# pi_ups.net
KiCad netlist of a schematic drawn in Altium Designer
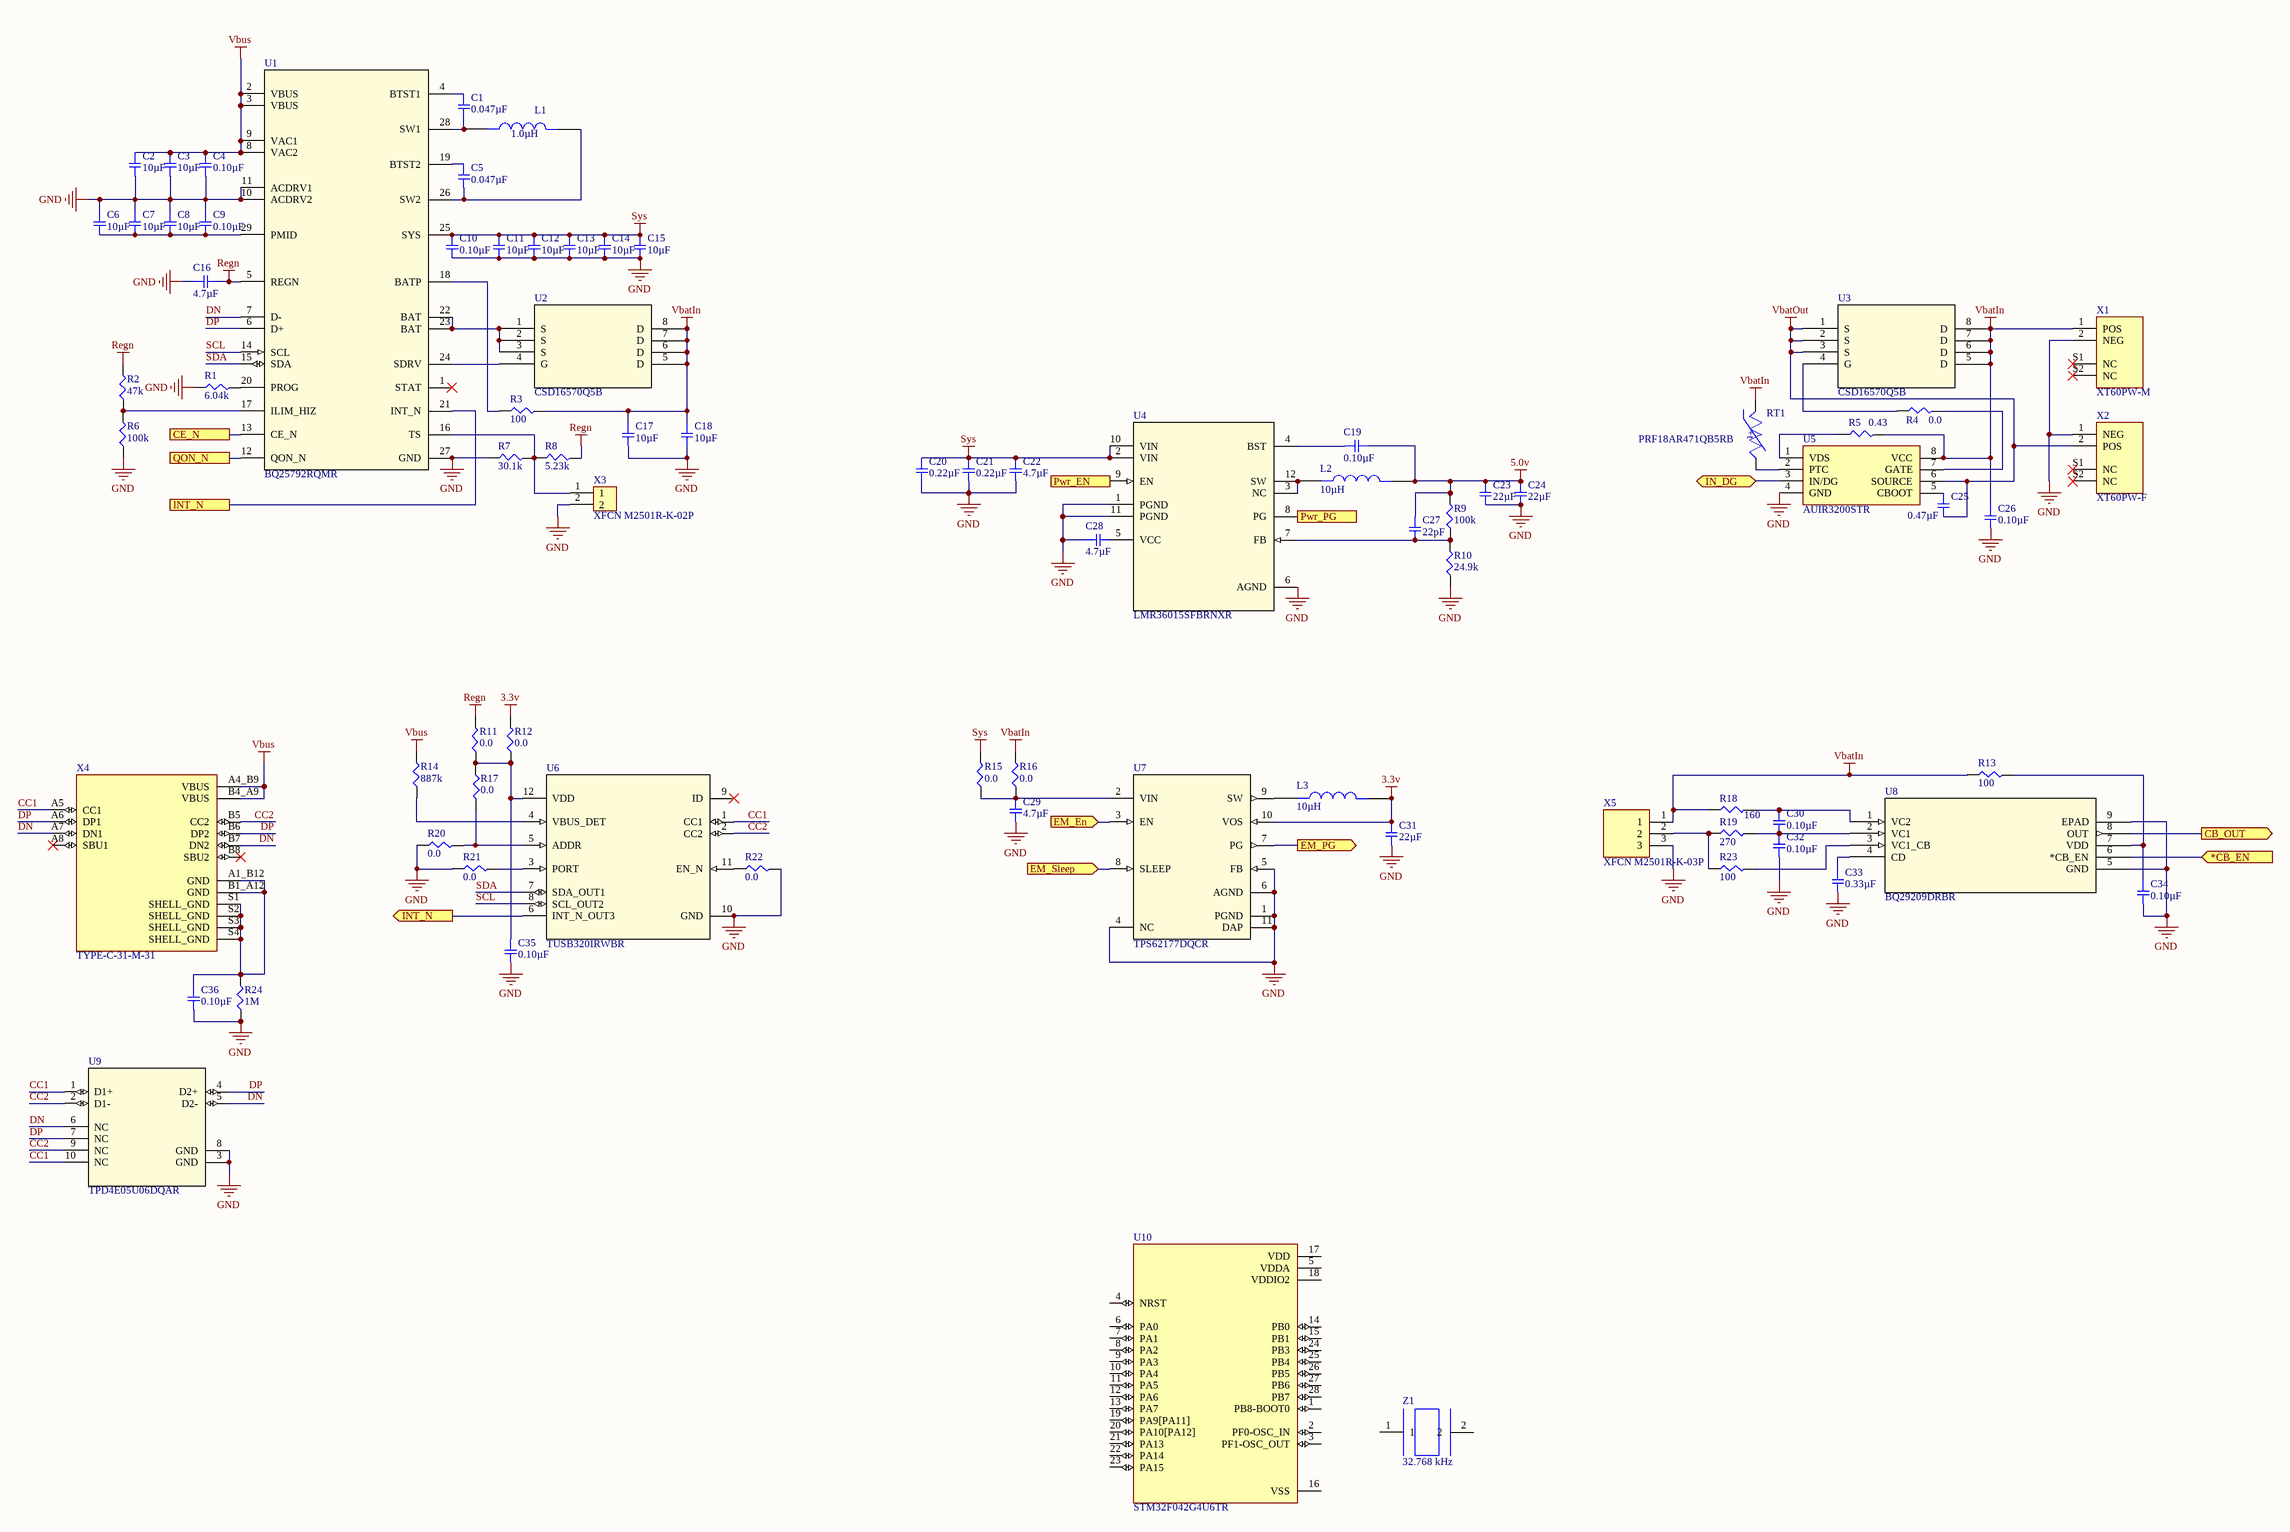
[diagram p0: pi_ups.SchDoc]

(export (version "E")
  (design (tool "Eeschema 10.0.6"))
  (components
    (comp (ref "C1")
      (value "0.047µF")
      (footprint "SMD-0402C")
      (description "CAP CER 0.047UF 50V X5R 0402")
      (fields
        (field (name "DIGI-KEY PART NUMBER") "490-12705-1-ND")
        (field (name "PART NUMBER") "GRM155R61H473KE19D")
      )
      (libsource (lib "capacitor_murata_0402") (part "GRM155R61H473KE19D"))
    )
    (comp (ref "C2")
      (value "10µF")
      (footprint "SMD-0805C")
      (description "CAP CER 10UF 35V X5R 0805")
      (fields
        (field (name "DIGI-KEY PART NUMBER") "490-10514-1-ND")
        (field (name "PART NUMBER") "GRM21BR6YA106KE43L")
      )
      (libsource (lib "capacitor_murata_0805") (part "GRM21BR6YA106KE43L"))
    )
    (comp (ref "C3")
      (value "10µF")
      (footprint "SMD-0805C")
      (description "CAP CER 10UF 35V X5R 0805")
      (fields
        (field (name "DIGI-KEY PART NUMBER") "490-10514-1-ND")
        (field (name "PART NUMBER") "GRM21BR6YA106KE43L")
      )
      (libsource (lib "capacitor_murata_0805") (part "GRM21BR6YA106KE43L"))
    )
    (comp (ref "C4")
      (value "0.10µF")
      (footprint "SMD-0402C")
      (description "CAP CER 0.1UF 50V X7R 0402")
      (fields
        (field (name "DIGI-KEY PART NUMBER") "490-10701-1-ND")
        (field (name "PART NUMBER") "GRM155R71H104ME14D")
      )
      (libsource (lib "capacitor_murata_0402") (part "GRM155R71H104ME14D"))
    )
    (comp (ref "C5")
      (value "0.047µF")
      (footprint "SMD-0402C")
      (description "CAP CER 0.047UF 50V X5R 0402")
      (fields
        (field (name "DIGI-KEY PART NUMBER") "490-12705-1-ND")
        (field (name "PART NUMBER") "GRM155R61H473KE19D")
      )
      (libsource (lib "capacitor_murata_0402") (part "GRM155R61H473KE19D"))
    )
    (comp (ref "C6")
      (value "10µF")
      (footprint "SMD-0805C")
      (description "CAP CER 10UF 35V X5R 0805")
      (fields
        (field (name "DIGI-KEY PART NUMBER") "490-10514-1-ND")
        (field (name "PART NUMBER") "GRM21BR6YA106KE43L")
      )
      (libsource (lib "capacitor_murata_0805") (part "GRM21BR6YA106KE43L"))
    )
    (comp (ref "C7")
      (value "10µF")
      (footprint "SMD-0805C")
      (description "CAP CER 10UF 35V X5R 0805")
      (fields
        (field (name "DIGI-KEY PART NUMBER") "490-10514-1-ND")
        (field (name "PART NUMBER") "GRM21BR6YA106KE43L")
      )
      (libsource (lib "capacitor_murata_0805") (part "GRM21BR6YA106KE43L"))
    )
    (comp (ref "C8")
      (value "10µF")
      (footprint "SMD-0805C")
      (description "CAP CER 10UF 35V X5R 0805")
      (fields
        (field (name "DIGI-KEY PART NUMBER") "490-10514-1-ND")
        (field (name "PART NUMBER") "GRM21BR6YA106KE43L")
      )
      (libsource (lib "capacitor_murata_0805") (part "GRM21BR6YA106KE43L"))
    )
    (comp (ref "C9")
      (value "0.10µF")
      (footprint "SMD-0402C")
      (description "CAP CER 0.1UF 50V X7R 0402")
      (fields
        (field (name "DIGI-KEY PART NUMBER") "490-10701-1-ND")
        (field (name "PART NUMBER") "GRM155R71H104ME14D")
      )
      (libsource (lib "capacitor_murata_0402") (part "GRM155R71H104ME14D"))
    )
    (comp (ref "C10")
      (value "0.10µF")
      (footprint "SMD-0402C")
      (description "CAP CER 0.1UF 50V X7R 0402")
      (fields
        (field (name "DIGI-KEY PART NUMBER") "490-10701-1-ND")
        (field (name "PART NUMBER") "GRM155R71H104ME14D")
      )
      (libsource (lib "capacitor_murata_0402") (part "GRM155R71H104ME14D"))
    )
    (comp (ref "C11")
      (value "10µF")
      (footprint "SMD-0805C")
      (description "CAP CER 10UF 35V X5R 0805")
      (fields
        (field (name "DIGI-KEY PART NUMBER") "490-10514-1-ND")
        (field (name "PART NUMBER") "GRM21BR6YA106KE43L")
      )
      (libsource (lib "capacitor_murata_0805") (part "GRM21BR6YA106KE43L"))
    )
    (comp (ref "C12")
      (value "10µF")
      (footprint "SMD-0805C")
      (description "CAP CER 10UF 35V X5R 0805")
      (fields
        (field (name "DIGI-KEY PART NUMBER") "490-10514-1-ND")
        (field (name "PART NUMBER") "GRM21BR6YA106KE43L")
      )
      (libsource (lib "capacitor_murata_0805") (part "GRM21BR6YA106KE43L"))
    )
    (comp (ref "C13")
      (value "10µF")
      (footprint "SMD-0805C")
      (description "CAP CER 10UF 35V X5R 0805")
      (fields
        (field (name "DIGI-KEY PART NUMBER") "490-10514-1-ND")
        (field (name "PART NUMBER") "GRM21BR6YA106KE43L")
      )
      (libsource (lib "capacitor_murata_0805") (part "GRM21BR6YA106KE43L"))
    )
    (comp (ref "C14")
      (value "10µF")
      (footprint "SMD-0805C")
      (description "CAP CER 10UF 35V X5R 0805")
      (fields
        (field (name "DIGI-KEY PART NUMBER") "490-10514-1-ND")
        (field (name "PART NUMBER") "GRM21BR6YA106KE43L")
      )
      (libsource (lib "capacitor_murata_0805") (part "GRM21BR6YA106KE43L"))
    )
    (comp (ref "C15")
      (value "10µF")
      (footprint "SMD-0805C")
      (description "CAP CER 10UF 35V X5R 0805")
      (fields
        (field (name "DIGI-KEY PART NUMBER") "490-10514-1-ND")
        (field (name "PART NUMBER") "GRM21BR6YA106KE43L")
      )
      (libsource (lib "capacitor_murata_0805") (part "GRM21BR6YA106KE43L"))
    )
    (comp (ref "C16")
      (value "4.7µF")
      (footprint "SMD-0805C")
      (description "CAP CER 4.7UF 50V X5R 0805")
      (fields
        (field (name "DIGI-KEY PART NUMBER") "490-10751-1-ND")
        (field (name "PART NUMBER") "GRM21BR61H475KE51L")
      )
      (libsource (lib "capacitor_murata_0805") (part "GRM21BR61H475KE51L"))
    )
    (comp (ref "C17")
      (value "10µF")
      (footprint "SMD-0805C")
      (description "CAP CER 10UF 35V X5R 0805")
      (fields
        (field (name "DIGI-KEY PART NUMBER") "490-10514-1-ND")
        (field (name "PART NUMBER") "GRM21BR6YA106KE43L")
      )
      (libsource (lib "capacitor_murata_0805") (part "GRM21BR6YA106KE43L"))
    )
    (comp (ref "C18")
      (value "10µF")
      (footprint "SMD-0805C")
      (description "CAP CER 10UF 35V X5R 0805")
      (fields
        (field (name "DIGI-KEY PART NUMBER") "490-10514-1-ND")
        (field (name "PART NUMBER") "GRM21BR6YA106KE43L")
      )
      (libsource (lib "capacitor_murata_0805") (part "GRM21BR6YA106KE43L"))
    )
    (comp (ref "C19")
      (value "0.10µF")
      (footprint "SMD-0402C")
      (description "CAP CER 0.1UF 50V X7R 0402")
      (fields
        (field (name "DIGI-KEY PART NUMBER") "490-10701-1-ND")
        (field (name "PART NUMBER") "GRM155R71H104ME14D")
      )
      (libsource (lib "capacitor_murata_0402") (part "GRM155R71H104ME14D"))
    )
    (comp (ref "C20")
      (value "0.22µF")
      (footprint "SMD-0603C")
      (description "CAP CER 0.22UF 50V X5R 0603")
      (fields
        (field (name "DIGI-KEY PART NUMBER") "490-12739-1-ND")
        (field (name "PART NUMBER") "GRM188R61H224KAC4D")
      )
      (libsource (lib "capacitor_murata_0603") (part "GRM188R61H224KAC4D"))
    )
    (comp (ref "C21")
      (value "0.22µF")
      (footprint "SMD-0603C")
      (description "CAP CER 0.22UF 50V X5R 0603")
      (fields
        (field (name "DIGI-KEY PART NUMBER") "490-12739-1-ND")
        (field (name "PART NUMBER") "GRM188R61H224KAC4D")
      )
      (libsource (lib "capacitor_murata_0603") (part "GRM188R61H224KAC4D"))
    )
    (comp (ref "C22")
      (value "4.7µF")
      (footprint "SMD-0805C")
      (description "CAP CER 4.7UF 50V X5R 0805")
      (fields
        (field (name "DIGI-KEY PART NUMBER") "490-10751-1-ND")
        (field (name "PART NUMBER") "GRM21BR61H475KE51L")
      )
      (libsource (lib "capacitor_murata_0805") (part "GRM21BR61H475KE51L"))
    )
    (comp (ref "C23")
      (value "22µF")
      (footprint "SMD-0805C")
      (description "CAP CER 22UF 10V X5R 0805")
      (fields
        (field (name "DIGI-KEY PART NUMBER") "490-9951-1-ND")
        (field (name "PART NUMBER") "GRM219R61A226MEA0D")
      )
      (libsource (lib "capacitor_murata_0805") (part "GRM219R61A226MEA0D"))
    )
    (comp (ref "C24")
      (value "22µF")
      (footprint "SMD-0805C")
      (description "CAP CER 22UF 10V X5R 0805")
      (fields
        (field (name "DIGI-KEY PART NUMBER") "490-9951-1-ND")
        (field (name "PART NUMBER") "GRM219R61A226MEA0D")
      )
      (libsource (lib "capacitor_murata_0805") (part "GRM219R61A226MEA0D"))
    )
    (comp (ref "C25")
      (value "0.47µF")
      (footprint "SMD-0603C")
      (description "CAP CER 0.47UF 16V X7R 0603")
      (fields
        (field (name "DIGI-KEY PART NUMBER") "490-4775-1-ND")
        (field (name "PART NUMBER") "GCM188R71C474KA55D")
      )
      (libsource (lib "capacitor_murata_0603") (part "GCM188R71C474KA55D"))
    )
    (comp (ref "C26")
      (value "0.10µF")
      (footprint "SMD-0402C")
      (description "CAP CER 0.1UF 50V X7R 0402")
      (fields
        (field (name "DIGI-KEY PART NUMBER") "490-10701-1-ND")
        (field (name "PART NUMBER") "GRM155R71H104ME14D")
      )
      (libsource (lib "capacitor_murata_0402") (part "GRM155R71H104ME14D"))
    )
    (comp (ref "C27")
      (value "22pF")
      (footprint "SMD-0402C")
      (description "CAP CER 22PF 50V NP0 0402")
      (fields
        (field (name "DIGI-KEY PART NUMBER") "490-9648-1-ND")
        (field (name "PART NUMBER") "GCM1555C1H220JA16D")
      )
      (libsource (lib "capacitor_murata_0402") (part "GCM1555C1H220JA16D"))
    )
    (comp (ref "C28")
      (value "4.7µF")
      (footprint "SMD-0805C")
      (description "CAP CER 4.7UF 50V X5R 0805")
      (fields
        (field (name "DIGI-KEY PART NUMBER") "490-10751-1-ND")
        (field (name "PART NUMBER") "GRM21BR61H475KE51L")
      )
      (libsource (lib "capacitor_murata_0805") (part "GRM21BR61H475KE51L"))
    )
    (comp (ref "C29")
      (value "4.7µF")
      (footprint "SMD-0805C")
      (description "CAP CER 4.7UF 50V X5R 0805")
      (fields
        (field (name "DIGI-KEY PART NUMBER") "490-10751-1-ND")
        (field (name "PART NUMBER") "GRM21BR61H475KE51L")
      )
      (libsource (lib "capacitor_murata_0805") (part "GRM21BR61H475KE51L"))
    )
    (comp (ref "C30")
      (value "0.10µF")
      (footprint "SMD-0402C")
      (description "CAP CER 0.1UF 50V X7R 0402")
      (fields
        (field (name "DIGI-KEY PART NUMBER") "490-10701-1-ND")
        (field (name "PART NUMBER") "GRM155R71H104ME14D")
      )
      (libsource (lib "capacitor_murata_0402") (part "GRM155R71H104ME14D"))
    )
    (comp (ref "C31")
      (value "22µF")
      (footprint "SMD-0805C")
      (description "CAP CER 22UF 10V X5R 0805")
      (fields
        (field (name "DIGI-KEY PART NUMBER") "490-9951-1-ND")
        (field (name "PART NUMBER") "GRM219R61A226MEA0D")
      )
      (libsource (lib "capacitor_murata_0805") (part "GRM219R61A226MEA0D"))
    )
    (comp (ref "C32")
      (value "0.10µF")
      (footprint "SMD-0402C")
      (description "CAP CER 0.1UF 50V X7R 0402")
      (fields
        (field (name "DIGI-KEY PART NUMBER") "490-10701-1-ND")
        (field (name "PART NUMBER") "GRM155R71H104ME14D")
      )
      (libsource (lib "capacitor_murata_0402") (part "GRM155R71H104ME14D"))
    )
    (comp (ref "C33")
      (value "0.33µF")
      (footprint "SMD-0603C")
      (description "CAP CER 0.33UF 16V X7R 0603")
      (fields
        (field (name "DIGI-KEY PART NUMBER") "490-6050-1-ND")
        (field (name "PART NUMBER") "GCM188R71C334KA37D")
      )
      (libsource (lib "capacitor_murata_0603") (part "GCM188R71C334KA37D"))
    )
    (comp (ref "C34")
      (value "0.10µF")
      (footprint "SMD-0402C")
      (description "CAP CER 0.1UF 50V X7R 0402")
      (fields
        (field (name "DIGI-KEY PART NUMBER") "490-10701-1-ND")
        (field (name "PART NUMBER") "GRM155R71H104ME14D")
      )
      (libsource (lib "capacitor_murata_0402") (part "GRM155R71H104ME14D"))
    )
    (comp (ref "C35")
      (value "0.10µF")
      (footprint "SMD-0402C")
      (description "CAP CER 0.1UF 50V X7R 0402")
      (fields
        (field (name "DIGI-KEY PART NUMBER") "490-10701-1-ND")
        (field (name "PART NUMBER") "GRM155R71H104ME14D")
      )
      (libsource (lib "capacitor_murata_0402") (part "GRM155R71H104ME14D"))
    )
    (comp (ref "C36")
      (value "0.10µF")
      (footprint "SMD-0402C")
      (description "CAP CER 0.1UF 50V X7R 0402")
      (fields
        (field (name "DIGI-KEY PART NUMBER") "490-10701-1-ND")
        (field (name "PART NUMBER") "GRM155R71H104ME14D")
      )
      (libsource (lib "capacitor_murata_0402") (part "GRM155R71H104ME14D"))
    )
    (comp (ref "L1")
      (value "1.0µH")
      (footprint "SPM6530T-1R0M120")
      (description "Shielded Wirewound Inductor 1.0uH 13.2A 0.0071ohms 7.1x6.5x3mm")
      (fields (field (name "PART NUMBER") "SPM6530T-1R0M120") (field (name "MANUFACTURER") "TDK"))
      (libsource (lib "common") (part "SPM6530T-1R0M120"))
    )
    (comp (ref "L2")
      (value "10µH")
      (footprint "4020")
      (description "1.9A 10uH ±20% 1.9A 165mΩ SMD,4.5x4.1x1.8mm Inductors (SMD) ROHS")
      (fields (field (name "MANUFACTURER") "KOHERelec") (field (name "PART NUMBER") "MDA4020-100M"))
      (libsource (lib "common") (part "MDA4020-100M"))
    )
    (comp (ref "L3")
      (value "10µH")
      (footprint "4020")
      (description "1.9A 10uH ±20% 1.9A 165mΩ SMD,4.5x4.1x1.8mm Inductors (SMD) ROHS")
      (fields (field (name "MANUFACTURER") "KOHERelec") (field (name "PART NUMBER") "MDA4020-100M"))
      (libsource (lib "common") (part "MDA4020-100M"))
    )
    (comp (ref "R1")
      (value "6.04k")
      (footprint "SMD-0402-RES")
      (description "RES SMD 6.04K OHM 1% 1/10W 0402")
      (fields
        (field (name "PART NUMBER") "ERJ-2RKF6041X")
        (field (name "DIGI-KEY PART NUMBER") "P6.04KLCT-ND")
      )
      (libsource (lib "Panasonic_ERJ_0402") (part "ERJ-2RKF6041X"))
    )
    (comp (ref "R2")
      (value "47k")
      (footprint "SMD-0402-RES")
      (description "RES SMD 47K OHM 1% 1/10W 0402")
      (fields
        (field (name "PART NUMBER") "ERJ-2RKF4702X")
        (field (name "DIGI-KEY PART NUMBER") "P47.0KLCT-ND")
      )
      (libsource (lib "Panasonic_ERJ_0402") (part "ERJ-2RKF4702X"))
    )
    (comp (ref "R3")
      (value "100")
      (footprint "SMD-0402-RES")
      (description "RES SMD 100 OHM 5% 1/5W 0402")
      (fields (field (name "PART NUMBER") "ERJ-PA2J101X") (field (name "DIGI-KEY PART NUMBER") "P17187CT-ND"))
      (libsource (lib "Panasonic_ERJ_0402") (part "ERJ-PA2J101X"))
    )
    (comp (ref "R4")
      (value "0.0")
      (footprint "SMD-0402-RES")
      (description "RES SMD 0.0OHM JUMPER 1/10W 0402")
      (fields (field (name "PART NUMBER") "ERJ-2GE0R00X") (field (name "DIGI-KEY PART NUMBER") "P0.0JCT-ND"))
      (libsource (lib "Panasonic_ERJ_0402") (part "ERJ-2GE0R00X"))
    )
    (comp (ref "R5")
      (value "0.43")
      (footprint "SMD-0402-RES")
      (description "RES SMD 0.43 OHM 1% 1/6W 0402")
      (fields (field (name "PART NUMBER") "ERJ-2BQFR43X") (field (name "DIGI-KEY PART NUMBER") "P.43AKCT-ND"))
      (libsource (lib "Panasonic_ERJ_0402") (part "ERJ-2BQFR43X"))
    )
    (comp (ref "R6")
      (value "100k")
      (footprint "SMD-0402-RES")
      (description "RES SMD 100K OHM 1% 1/10W 0402")
      (fields
        (field (name "PART NUMBER") "ERJ-2RKF1003X")
        (field (name "DIGI-KEY PART NUMBER") "P100KLCT-ND")
      )
      (libsource (lib "Panasonic_ERJ_0402") (part "ERJ-2RKF1003X"))
    )
    (comp (ref "R7")
      (value "30.1k")
      (footprint "SMD-0402-RES")
      (description "RES SMD 30.1K OHM 1% 1/10W 0402")
      (fields
        (field (name "PART NUMBER") "ERJ-2RKF3012X")
        (field (name "DIGI-KEY PART NUMBER") "P30.1KLCT-ND")
      )
      (libsource (lib "Panasonic_ERJ_0402") (part "ERJ-2RKF3012X"))
    )
    (comp (ref "R8")
      (value "5.23k")
      (footprint "SMD-0402-RES")
      (description "RES SMD 5.23K OHM 1% 1/10W 0402")
      (fields
        (field (name "PART NUMBER") "ERJ-2RKF5231X")
        (field (name "DIGI-KEY PART NUMBER") "P5.23KLCT-ND")
      )
      (libsource (lib "Panasonic_ERJ_0402") (part "ERJ-2RKF5231X"))
    )
    (comp (ref "R9")
      (value "100k")
      (footprint "SMD-0402-RES")
      (description "RES SMD 100K OHM 1% 1/10W 0402")
      (fields
        (field (name "PART NUMBER") "ERJ-2RKF1003X")
        (field (name "DIGI-KEY PART NUMBER") "P100KLCT-ND")
      )
      (libsource (lib "Panasonic_ERJ_0402") (part "ERJ-2RKF1003X"))
    )
    (comp (ref "R10")
      (value "24.9k")
      (footprint "SMD-0402-RES")
      (description "RES SMD 24.9K OHM 1% 1/10W 0402")
      (fields
        (field (name "PART NUMBER") "ERJ-2RKF2492X")
        (field (name "DIGI-KEY PART NUMBER") "P24.9KLCT-ND")
      )
      (libsource (lib "Panasonic_ERJ_0402") (part "ERJ-2RKF2492X"))
    )
    (comp (ref "R11")
      (value "0.0")
      (footprint "SMD-0402-RES")
      (description "RES SMD 0.0OHM JUMPER 1/10W 0402")
      (fields (field (name "PART NUMBER") "ERJ-2GE0R00X") (field (name "DIGI-KEY PART NUMBER") "P0.0JCT-ND"))
      (libsource (lib "Panasonic_ERJ_0402") (part "ERJ-2GE0R00X"))
    )
    (comp (ref "R12")
      (value "0.0")
      (footprint "SMD-0402-RES")
      (description "RES SMD 0.0OHM JUMPER 1/10W 0402")
      (fields (field (name "PART NUMBER") "ERJ-2GE0R00X") (field (name "DIGI-KEY PART NUMBER") "P0.0JCT-ND"))
      (libsource (lib "Panasonic_ERJ_0402") (part "ERJ-2GE0R00X"))
    )
    (comp (ref "R13")
      (value "100")
      (footprint "SMD-0402-RES")
      (description "RES SMD 100 OHM 5% 1/5W 0402")
      (fields (field (name "PART NUMBER") "ERJ-PA2J101X") (field (name "DIGI-KEY PART NUMBER") "P17187CT-ND"))
      (libsource (lib "Panasonic_ERJ_0402") (part "ERJ-PA2J101X"))
    )
    (comp (ref "R14")
      (value "887k")
      (footprint "SMD-0402-RES")
      (description "RES SMD 887K OHM 1% 1/10W 0402")
      (fields
        (field (name "PART NUMBER") "ERJ-2RKF8873X")
        (field (name "DIGI-KEY PART NUMBER") "P887KLCT-ND")
      )
      (libsource (lib "Panasonic_ERJ_0402") (part "ERJ-2RKF8873X"))
    )
    (comp (ref "R15")
      (value "0.0")
      (footprint "SMD-0402-RES")
      (description "RES SMD 0.0OHM JUMPER 1/10W 0402")
      (fields (field (name "PART NUMBER") "ERJ-2GE0R00X") (field (name "DIGI-KEY PART NUMBER") "P0.0JCT-ND"))
      (libsource (lib "Panasonic_ERJ_0402") (part "ERJ-2GE0R00X"))
    )
    (comp (ref "R16")
      (value "0.0")
      (footprint "SMD-0402-RES")
      (description "RES SMD 0.0OHM JUMPER 1/10W 0402")
      (fields (field (name "PART NUMBER") "ERJ-2GE0R00X") (field (name "DIGI-KEY PART NUMBER") "P0.0JCT-ND"))
      (libsource (lib "Panasonic_ERJ_0402") (part "ERJ-2GE0R00X"))
    )
    (comp (ref "R17")
      (value "0.0")
      (footprint "SMD-0402-RES")
      (description "RES SMD 0.0OHM JUMPER 1/10W 0402")
      (fields (field (name "PART NUMBER") "ERJ-2GE0R00X") (field (name "DIGI-KEY PART NUMBER") "P0.0JCT-ND"))
      (libsource (lib "Panasonic_ERJ_0402") (part "ERJ-2GE0R00X"))
    )
    (comp (ref "R18")
      (value "160")
      (footprint "SMD-0402-RES")
      (description "RES SMD 160 OHM 5% 1/10W 0402")
      (fields (field (name "PART NUMBER") "ERJ-2GEJ161X") (field (name "DIGI-KEY PART NUMBER") "P160JCT-ND"))
      (libsource (lib "Panasonic_ERJ_0402") (part "ERJ-2GEJ161X"))
    )
    (comp (ref "R19")
      (value "270")
      (footprint "SMD-0402-RES")
      (description "RES SMD 270 OHM 5% 1/10W 0402")
      (fields (field (name "PART NUMBER") "ERJ-2GEJ271X") (field (name "DIGI-KEY PART NUMBER") "P270JCT-ND"))
      (libsource (lib "Panasonic_ERJ_0402") (part "ERJ-2GEJ271X"))
    )
    (comp (ref "R20")
      (value "0.0")
      (footprint "SMD-0402-RES")
      (description "RES SMD 0.0OHM JUMPER 1/10W 0402")
      (fields (field (name "PART NUMBER") "ERJ-2GE0R00X") (field (name "DIGI-KEY PART NUMBER") "P0.0JCT-ND"))
      (libsource (lib "Panasonic_ERJ_0402") (part "ERJ-2GE0R00X"))
    )
    (comp (ref "R21")
      (value "0.0")
      (footprint "SMD-0402-RES")
      (description "RES SMD 0.0OHM JUMPER 1/10W 0402")
      (fields (field (name "PART NUMBER") "ERJ-2GE0R00X") (field (name "DIGI-KEY PART NUMBER") "P0.0JCT-ND"))
      (libsource (lib "Panasonic_ERJ_0402") (part "ERJ-2GE0R00X"))
    )
    (comp (ref "R22")
      (value "0.0")
      (footprint "SMD-0402-RES")
      (description "RES SMD 0.0OHM JUMPER 1/10W 0402")
      (fields (field (name "PART NUMBER") "ERJ-2GE0R00X") (field (name "DIGI-KEY PART NUMBER") "P0.0JCT-ND"))
      (libsource (lib "Panasonic_ERJ_0402") (part "ERJ-2GE0R00X"))
    )
    (comp (ref "R23")
      (value "100")
      (footprint "SMD-0402-RES")
      (description "RES SMD 100 OHM 5% 1/5W 0402")
      (fields (field (name "PART NUMBER") "ERJ-PA2J101X") (field (name "DIGI-KEY PART NUMBER") "P17187CT-ND"))
      (libsource (lib "Panasonic_ERJ_0402") (part "ERJ-PA2J101X"))
    )
    (comp (ref "R24")
      (value "1M")
      (footprint "SMD-0402-RES")
      (description "RES SMD 1M OHM 5% 1/5W 0402")
      (fields (field (name "PART NUMBER") "ERJ-PA2J105X") (field (name "DIGI-KEY PART NUMBER") "P17211CT-ND"))
      (libsource (lib "Panasonic_ERJ_0402") (part "ERJ-PA2J105X"))
    )
    (comp (ref "RT1")
      (value "PRF18AR471QB5RB")
      (footprint "THRMC1608X95N")
      (description "PTC Thermistor 470 Ohms 0603 (1608 Metric)")
      (fields
        (field (name "MANUFACTURER") "Murata Electronics North America")
        (field (name "LCSC PART NUMBER") "C152554")
      )
      (libsource (lib "common") (part "PRF18AR471QB5RB"))
    )
    (comp (ref "U1")
      (value "BQ25792RQMR")
      (footprint "RQM0029A-MFG")
      (fields
        (field (name "MANUFACTURER") "Texas Instruments")
        (field (name "LCSC PART NUMBER") "C2862876")
        (field (name "COPYRIGHT") "Copyright (C) 2022 Ultra Librarian. All rights reserved.")
      )
      (libsource (lib "chips") (part "BQ25792RQMR"))
    )
    (comp (ref "U2")
      (value "CSD16570Q5B")
      (footprint "DNK8")
      (description "25-V, N channel NexFET™ power MOSFET, single SON 5 mm x 6 mm, 0.82 mOhm")
      (fields
        (field (name "MANUFACTURER") "Texas Instruments")
        (field (name "LCSC PART NUMBER") "C473359")
        (field (name "COPYRIGHT") "Copyright (C) 2022 Ultra Librarian. All rights reserved.")
      )
      (libsource (lib "chips") (part "CSD16570Q5B"))
    )
    (comp (ref "U3")
      (value "CSD16570Q5B")
      (footprint "DNK8")
      (description "25-V, N channel NexFET™ power MOSFET, single SON 5 mm x 6 mm, 0.82 mOhm")
      (fields
        (field (name "MANUFACTURER") "Texas Instruments")
        (field (name "LCSC PART NUMBER") "C473359")
        (field (name "COPYRIGHT") "Copyright (C) 2022 Ultra Librarian. All rights reserved.")
      )
      (libsource (lib "chips") (part "CSD16570Q5B"))
    )
    (comp (ref "U4")
      (value "LMR36015SFBRNXR")
      (footprint "RNX0012B")
      (description "4.2-V to 60-V, 1.5-A ultra-small synchronous step-down converter with extended temperature")
      (fields
        (field (name "MANUFACTURER") "Texas Instruments")
        (field (name "COPYRIGHT") "Copyright (C) 2022 Ultra Librarian. All rights reserved.")
      )
      (libsource (lib "chips") (part "LMR36015SFBRNXR"))
    )
    (comp (ref "U5")
      (value "AUIR3200STR")
      (footprint "SOIC127P600X175-8N")
      (fields
        (field (name "MANUFACTURER") "Infineon Technologies")
        (field (name "LCSC PART NUMBER") "C97698")
      )
      (libsource (lib "chips") (part "AUIR3200STR"))
    )
    (comp (ref "U6")
      (value "TUSB320IRWBR")
      (footprint "RWB0012A")
      (description "USB Type-C configuration channel logic and port control")
      (fields
        (field (name "MANUFACTURER") "Texas Instruments")
        (field (name "LCSC PART NUMBER") "C80170")
        (field (name "COPYRIGHT") "Copyright (C) 2022 Ultra Librarian. All rights reserved.")
      )
      (libsource (lib "chips") (part "TUSB320IRWBR"))
    )
    (comp (ref "U7")
      (value "TPS62177DQCR")
      (footprint "DQC0010A")
      (description "28V, 0.5A Step-Down Converter with SNOOZE Mode")
      (fields
        (field (name "MANUFACTURER") "Texas Instruments")
        (field (name "LCSC PART NUMBER") "C91241")
        (field (name "COPYRIGHT") "Copyright (C) 2022 Ultra Librarian. All rights reserved.")
      )
      (libsource (lib "chips") (part "TPS62177DQCR"))
    )
    (comp (ref "U8")
      (value "BQ29209DRBR")
      (footprint "DRB8_1P6X2P4")
      (description "Voltage Protection with Automatic Cell Balance For 2-Cell Li-Ion Batteries, OVP=4.30V")
      (fields
        (field (name "MANUFACTURER") "Texas Instruments")
        (field (name "LCSC PART NUMBER") "C139352")
        (field (name "COPYRIGHT") "Copyright (C) 2022 Ultra Librarian. All rights reserved.")
      )
      (libsource (lib "chips") (part "BQ29209DRBR"))
    )
    (comp (ref "U9")
      (value "TPD4E05U06DQAR")
      (footprint "DQA0010A")
      (description "Quad 0.5-pF, 5.5-V, ±12-kV ESD protection diode for USB,  HDMI & High Speed Interfaces")
      (fields
        (field (name "MANUFACTURER") "Texas Instruments")
        (field (name "LCSC PART NUMBER") "C138714")
        (field (name "COPYRIGHT") "Copyright (C) 2022 Ultra Librarian. All rights reserved.")
      )
      (libsource (lib "chips") (part "TPD4E05U06DQAR"))
    )
    (comp (ref "U10")
      (value "STM32F042G4U6TR")
      (footprint "IC_STM32F042G4U6TR")
      (description "ARM® Cortex®-M0 STM32F0 Microcontroller IC 32-Bit 48MHz 32KB (32K x 8) FLASH 28-UFQFPN (4x4)")
      (fields (field (name "MANUFACTURER") "STMicroelectronics") (field (name "LCSC PART NUMBER") "C88048"))
      (libsource (lib "chips") (part "STM32F042G4U6TR"))
    )
    (comp (ref "X1")
      (value "XT60PW-M")
      (footprint "XT60PW-M")
      (description "Socket, DC supply, male, PIN: 2")
      (fields (field (name "MANUFACTURER") "AMASS") (field (name "LCSC PART NUMBER") "C98732"))
      (libsource (lib "XT60PW") (part "XT60PW-M"))
    )
    (comp (ref "X2")
      (value "XT60PW-F")
      (footprint "XT60PW-F")
      (description "Socket DC Supply Connector Female")
      (fields (field (name "MANUFACTURER") "AMASS"))
      (libsource (lib "XT60PW") (part "XT60PW-F"))
    )
    (comp (ref "X3")
      (value "XFCN M2501R-K-02P")
      (footprint "JST_S2B-XH-A(LF)(SN)")
      (description "Connector Header Through Hole, Right Angle 2 position 0.098 (2.50mm)")
      (fields (field (name "PART NUMBER") "M2501R-K-02P") (field (name "MANUFACTURER") "XFCN"))
      (libsource (lib "JST") (part "XFCN M2501R-K-02P"))
    )
    (comp (ref "X4")
      (value "TYPE-C-31-M-31")
      (footprint "TYPE-C-31-M-31")
      (description "5A 1 Surface Mount 16 Female -30℃~+80℃ Type-C SMD USB Connectors ROHS")
      (fields
        (field (name "MANUFACTURER") "Korean Hroparts Elec")
        (field (name "LCSC PART NUMBER") "C2760486")
      )
      (libsource (lib "Type-C") (part "TYPE-C-31-M-31"))
    )
    (comp (ref "X5")
      (value "XFCN M2501R-K-03P")
      (footprint "JST_S3B-XH-A(LF)(SN)")
      (description "Connector Header Through Hole, Right Angle 3 position 0.098 (2.50mm)")
      (fields (field (name "PART NUMBER") "M2501R-K-03P") (field (name "MANUFACTURER") "XFCN"))
      (libsource (lib "JST") (part "XFCN M2501R-K-03P"))
    )
    (comp (ref "Z1")
      (value "32.768 kHz")
      (footprint "SnapEDApcb:XTAL320X150X90")
      (description "32.768kHz SMD Crystal Resonator 12.5pF 90kΩ ±20ppm -40℃~+85℃ SMD2012-2P Crystals ROHS")
      (fields (field (name "PART NUMBER") "FC-12M 32.7680KA-A5") (field (name "MANUFACTURER") "Seiko Epson"))
      (libsource (lib "common") (part "FC-12M 32.7680KA-A5"))
    )
  )
  (nets
    (net (code "1") (name "/*CB_EN") (class "Default")
      (node (ref "U8") (pin "6") (pinfunction "*CB_EN_6") (pintype "passive"))
    )
    (net (code "2") (name "/CB_OUT") (class "Default")
      (node (ref "U8") (pin "8") (pinfunction "OUT_8") (pintype "output"))
    )
    (net (code "3") (name "/CC1") (class "Default")
      (node (ref "U6") (pin "1") (pinfunction "CC1_1") (pintype "bidirectional"))
      (node (ref "U9") (pin "1") (pinfunction "D1+_1") (pintype "bidirectional"))
      (node (ref "U9") (pin "10") (pinfunction "NC_10") (pintype "passive"))
      (node (ref "X4") (pin "A5") (pinfunction "CC1_A5") (pintype "bidirectional"))
    )
    (net (code "4") (name "/CC2") (class "Default")
      (node (ref "U6") (pin "2") (pinfunction "CC2_2") (pintype "bidirectional"))
      (node (ref "U9") (pin "2") (pinfunction "D1-_2") (pintype "bidirectional"))
      (node (ref "U9") (pin "9") (pinfunction "NC_9") (pintype "passive"))
      (node (ref "X4") (pin "B5") (pinfunction "CC2_B5") (pintype "bidirectional"))
    )
    (net (code "5") (name "/CE_N") (class "Default")
      (node (ref "U1") (pin "13") (pinfunction "CE_N_13") (pintype "passive"))
    )
    (net (code "6") (name "/DN") (class "Default")
      (node (ref "U1") (pin "7") (pinfunction "D-_7") (pintype "passive"))
      (node (ref "U9") (pin "5") (pinfunction "D2-_5") (pintype "bidirectional"))
      (node (ref "U9") (pin "6") (pinfunction "NC_6") (pintype "passive"))
      (node (ref "X4") (pin "A7") (pinfunction "DN1_A7") (pintype "bidirectional"))
      (node (ref "X4") (pin "B7") (pinfunction "DN2_B7") (pintype "bidirectional"))
    )
    (net (code "7") (name "/DP") (class "Default")
      (node (ref "U1") (pin "6") (pinfunction "D+_6") (pintype "passive"))
      (node (ref "U9") (pin "4") (pinfunction "D2+_4") (pintype "bidirectional"))
      (node (ref "U9") (pin "7") (pinfunction "NC_7") (pintype "passive"))
      (node (ref "X4") (pin "A6") (pinfunction "DP1_A6") (pintype "bidirectional"))
      (node (ref "X4") (pin "B6") (pinfunction "DP2_B6") (pintype "bidirectional"))
    )
    (net (code "8") (name "/EM_En") (class "Default")
      (node (ref "U7") (pin "3") (pinfunction "EN_3") (pintype "input"))
    )
    (net (code "9") (name "/EM_PG") (class "Default")
      (node (ref "U7") (pin "7") (pinfunction "PG_7") (pintype "output"))
    )
    (net (code "10") (name "/EM_Sleep") (class "Default")
      (node (ref "U7") (pin "8") (pinfunction "SLEEP_8") (pintype "input"))
    )
    (net (code "11") (name "/INT_N") (class "Default")
      (node (ref "U1") (pin "21") (pinfunction "INT_N_21") (pintype "passive"))
      (node (ref "U6") (pin "6") (pinfunction "INT_N_OUT3_6") (pintype "open_collector"))
    )
    (net (code "12") (name "/IN_DG") (class "Default")
      (node (ref "U5") (pin "3") (pinfunction "IN/DG_3") (pintype "passive"))
    )
    (net (code "13") (name "/Pwr_EN") (class "Default")
      (node (ref "U4") (pin "9") (pinfunction "EN_9") (pintype "input"))
    )
    (net (code "14") (name "/Pwr_PG") (class "Default")
      (node (ref "U4") (pin "8") (pinfunction "PG_8") (pintype "open_collector"))
    )
    (net (code "15") (name "/QON_N") (class "Default")
      (node (ref "U1") (pin "12") (pinfunction "QON_N_12") (pintype "passive"))
    )
    (net (code "16") (name "/SCL") (class "Default")
      (node (ref "U1") (pin "14") (pinfunction "SCL_14") (pintype "input"))
      (node (ref "U6") (pin "8") (pinfunction "SCL_OUT2_8") (pintype "bidirectional"))
    )
    (net (code "17") (name "/SDA") (class "Default")
      (node (ref "U1") (pin "15") (pinfunction "SDA_15") (pintype "bidirectional"))
      (node (ref "U6") (pin "7") (pinfunction "SDA_OUT1_7") (pintype "bidirectional"))
    )
    (net (code "18") (name "3.3v") (class "Default")
      (node (ref "C31") (pin "1") (pinfunction "1_1") (pintype "passive"))
      (node (ref "L3") (pin "2") (pinfunction "2_2") (pintype "passive"))
      (node (ref "R12") (pin "2") (pinfunction "2_2") (pintype "passive"))
      (node (ref "U7") (pin "10") (pinfunction "VOS_10") (pintype "input"))
    )
    (net (code "19") (name "5.0v") (class "Default")
      (node (ref "C19") (pin "2") (pinfunction "2_2") (pintype "passive"))
      (node (ref "C23") (pin "1") (pinfunction "1_1") (pintype "passive"))
      (node (ref "C24") (pin "1") (pinfunction "1_1") (pintype "passive"))
      (node (ref "C27") (pin "1") (pinfunction "1_1") (pintype "passive"))
      (node (ref "L2") (pin "2") (pinfunction "2_2") (pintype "passive"))
      (node (ref "R9") (pin "2") (pinfunction "2_2") (pintype "passive"))
    )
    (net (code "20") (name "GND") (class "Default")
      (node (ref "C10") (pin "2") (pinfunction "2_2") (pintype "passive"))
      (node (ref "C11") (pin "2") (pinfunction "2_2") (pintype "passive"))
      (node (ref "C12") (pin "2") (pinfunction "2_2") (pintype "passive"))
      (node (ref "C13") (pin "2") (pinfunction "2_2") (pintype "passive"))
      (node (ref "C14") (pin "2") (pinfunction "2_2") (pintype "passive"))
      (node (ref "C15") (pin "2") (pinfunction "2_2") (pintype "passive"))
      (node (ref "C16") (pin "1") (pinfunction "1_1") (pintype "passive"))
      (node (ref "C17") (pin "2") (pinfunction "2_2") (pintype "passive"))
      (node (ref "C18") (pin "2") (pinfunction "2_2") (pintype "passive"))
      (node (ref "C2") (pin "2") (pinfunction "2_2") (pintype "passive"))
      (node (ref "C20") (pin "2") (pinfunction "2_2") (pintype "passive"))
      (node (ref "C21") (pin "2") (pinfunction "2_2") (pintype "passive"))
      (node (ref "C22") (pin "2") (pinfunction "2_2") (pintype "passive"))
      (node (ref "C23") (pin "2") (pinfunction "2_2") (pintype "passive"))
      (node (ref "C24") (pin "2") (pinfunction "2_2") (pintype "passive"))
      (node (ref "C26") (pin "2") (pinfunction "2_2") (pintype "passive"))
      (node (ref "C28") (pin "1") (pinfunction "1_1") (pintype "passive"))
      (node (ref "C29") (pin "2") (pinfunction "2_2") (pintype "passive"))
      (node (ref "C3") (pin "2") (pinfunction "2_2") (pintype "passive"))
      (node (ref "C31") (pin "2") (pinfunction "2_2") (pintype "passive"))
      (node (ref "C32") (pin "2") (pinfunction "2_2") (pintype "passive"))
      (node (ref "C33") (pin "2") (pinfunction "2_2") (pintype "passive"))
      (node (ref "C34") (pin "2") (pinfunction "2_2") (pintype "passive"))
      (node (ref "C35") (pin "2") (pinfunction "2_2") (pintype "passive"))
      (node (ref "C36") (pin "2") (pinfunction "2_2") (pintype "passive"))
      (node (ref "C4") (pin "2") (pinfunction "2_2") (pintype "passive"))
      (node (ref "C6") (pin "1") (pinfunction "1_1") (pintype "passive"))
      (node (ref "C7") (pin "1") (pinfunction "1_1") (pintype "passive"))
      (node (ref "C8") (pin "1") (pinfunction "1_1") (pintype "passive"))
      (node (ref "C9") (pin "1") (pinfunction "1_1") (pintype "passive"))
      (node (ref "R1") (pin "1") (pinfunction "1_1") (pintype "passive"))
      (node (ref "R10") (pin "1") (pinfunction "1_1") (pintype "passive"))
      (node (ref "R20") (pin "1") (pinfunction "1_1") (pintype "passive"))
      (node (ref "R21") (pin "1") (pinfunction "1_1") (pintype "passive"))
      (node (ref "R22") (pin "2") (pinfunction "2_2") (pintype "passive"))
      (node (ref "R24") (pin "1") (pinfunction "1_1") (pintype "passive"))
      (node (ref "R6") (pin "1") (pinfunction "1_1") (pintype "passive"))
      (node (ref "R7") (pin "1") (pinfunction "1_1") (pintype "passive"))
      (node (ref "U1") (pin "10") (pinfunction "ACDRV2_10") (pintype "power_in"))
      (node (ref "U1") (pin "11") (pinfunction "ACDRV1_11") (pintype "power_in"))
      (node (ref "U1") (pin "27") (pinfunction "GND_27") (pintype "power_in"))
      (node (ref "U4") (pin "1") (pinfunction "PGND_1") (pintype "power_in"))
      (node (ref "U4") (pin "11") (pinfunction "PGND_11") (pintype "power_in"))
      (node (ref "U4") (pin "6") (pinfunction "AGND_6") (pintype "power_in"))
      (node (ref "U5") (pin "4") (pinfunction "GND_4") (pintype "passive"))
      (node (ref "U6") (pin "10") (pinfunction "GND_10") (pintype "power_in"))
      (node (ref "U7") (pin "1") (pinfunction "PGND_1") (pintype "power_in"))
      (node (ref "U7") (pin "11") (pinfunction "DAP_11") (pintype "power_in"))
      (node (ref "U7") (pin "4") (pinfunction "NC_4") (pintype "passive"))
      (node (ref "U7") (pin "5") (pinfunction "FB_5") (pintype "input"))
      (node (ref "U7") (pin "6") (pinfunction "AGND_6") (pintype "power_in"))
      (node (ref "U8") (pin "5") (pinfunction "GND_5") (pintype "power_in"))
      (node (ref "U8") (pin "9") (pinfunction "EPAD_9") (pintype "power_in"))
      (node (ref "U9") (pin "3") (pinfunction "GND_3") (pintype "power_in"))
      (node (ref "U9") (pin "8") (pinfunction "GND_8") (pintype "power_in"))
      (node (ref "X1") (pin "2") (pinfunction "NEG_2") (pintype "passive"))
      (node (ref "X2") (pin "1") (pinfunction "NEG_1") (pintype "passive"))
      (node (ref "X3") (pin "2") (pinfunction "2_2") (pintype "passive"))
      (node (ref "X5") (pin "3") (pinfunction "3_3") (pintype "passive"))
    )
    (net (code "21") (name "Net-(C36-Pad1)") (class "Default")
      (node (ref "C36") (pin "1") (pinfunction "1_1") (pintype "passive"))
      (node (ref "R24") (pin "2") (pinfunction "2_2") (pintype "passive"))
      (node (ref "X4") (pin "A1_B12") (pinfunction "GND_A1_B12") (pintype "power_in"))
      (node (ref "X4") (pin "B1_A12") (pinfunction "GND_B1_A12") (pintype "power_in"))
      (node (ref "X4") (pin "S1") (pinfunction "SHELL_GND_S1") (pintype "power_in"))
      (node (ref "X4") (pin "S2") (pinfunction "SHELL_GND_S2") (pintype "power_in"))
      (node (ref "X4") (pin "S3") (pinfunction "SHELL_GND_S3") (pintype "power_in"))
      (node (ref "X4") (pin "S4") (pinfunction "SHELL_GND_S4") (pintype "power_in"))
    )
    (net (code "22") (name "Net-(R19-Pad1)") (class "Default")
      (node (ref "R19") (pin "1") (pinfunction "1_1") (pintype "passive"))
      (node (ref "R23") (pin "1") (pinfunction "1_1") (pintype "passive"))
      (node (ref "X5") (pin "2") (pinfunction "2_2") (pintype "passive"))
    )
    (net (code "23") (name "Net-(U1-BAT-Pad22)") (class "Default")
      (node (ref "U1") (pin "22") (pinfunction "BAT_22") (pintype "passive"))
      (node (ref "U1") (pin "23") (pinfunction "BAT_23") (pintype "passive"))
      (node (ref "U2") (pin "1") (pinfunction "S_1") (pintype "passive"))
      (node (ref "U2") (pin "2") (pinfunction "S_2") (pintype "passive"))
      (node (ref "U2") (pin "3") (pinfunction "S_3") (pintype "passive"))
    )
    (net (code "24") (name "Net-(U1-BATP)") (class "Default")
      (node (ref "R3") (pin "1") (pinfunction "1_1") (pintype "passive"))
      (node (ref "U1") (pin "18") (pinfunction "BATP_18") (pintype "passive"))
    )
    (net (code "25") (name "Net-(U1-BTST1)") (class "Default")
      (node (ref "C1") (pin "1") (pinfunction "1_1") (pintype "passive"))
      (node (ref "U1") (pin "4") (pinfunction "BTST1_4") (pintype "passive"))
    )
    (net (code "26") (name "Net-(U1-BTST2)") (class "Default")
      (node (ref "C5") (pin "1") (pinfunction "1_1") (pintype "passive"))
      (node (ref "U1") (pin "19") (pinfunction "BTST2_19") (pintype "passive"))
    )
    (net (code "27") (name "Net-(U1-ILIM_HIZ)") (class "Default")
      (node (ref "R2") (pin "1") (pinfunction "1_1") (pintype "passive"))
      (node (ref "R6") (pin "2") (pinfunction "2_2") (pintype "passive"))
      (node (ref "U1") (pin "17") (pinfunction "ILIM_HIZ_17") (pintype "passive"))
    )
    (net (code "28") (name "Net-(U1-PMID)") (class "Default")
      (node (ref "C6") (pin "2") (pinfunction "2_2") (pintype "passive"))
      (node (ref "C7") (pin "2") (pinfunction "2_2") (pintype "passive"))
      (node (ref "C8") (pin "2") (pinfunction "2_2") (pintype "passive"))
      (node (ref "C9") (pin "2") (pinfunction "2_2") (pintype "passive"))
      (node (ref "U1") (pin "29") (pinfunction "PMID_29") (pintype "passive"))
    )
    (net (code "29") (name "Net-(U1-PROG)") (class "Default")
      (node (ref "R1") (pin "2") (pinfunction "2_2") (pintype "passive"))
      (node (ref "U1") (pin "20") (pinfunction "PROG_20") (pintype "passive"))
    )
    (net (code "30") (name "Net-(U1-SDRV)") (class "Default")
      (node (ref "U1") (pin "24") (pinfunction "SDRV_24") (pintype "passive"))
      (node (ref "U2") (pin "4") (pinfunction "G_4") (pintype "passive"))
    )
    (net (code "31") (name "Net-(U1-SW1)") (class "Default")
      (node (ref "C1") (pin "2") (pinfunction "2_2") (pintype "passive"))
      (node (ref "L1") (pin "1") (pinfunction "1_1") (pintype "passive"))
      (node (ref "U1") (pin "28") (pinfunction "SW1_28") (pintype "passive"))
    )
    (net (code "32") (name "Net-(U1-SW2)") (class "Default")
      (node (ref "C5") (pin "2") (pinfunction "2_2") (pintype "passive"))
      (node (ref "L1") (pin "2") (pinfunction "2_2") (pintype "passive"))
      (node (ref "U1") (pin "26") (pinfunction "SW2_26") (pintype "passive"))
    )
    (net (code "33") (name "Net-(U1-TS)") (class "Default")
      (node (ref "R7") (pin "2") (pinfunction "2_2") (pintype "passive"))
      (node (ref "R8") (pin "1") (pinfunction "1_1") (pintype "passive"))
      (node (ref "U1") (pin "16") (pinfunction "TS_16") (pintype "passive"))
      (node (ref "X3") (pin "1") (pinfunction "1_1") (pintype "passive"))
    )
    (net (code "34") (name "Net-(U3-G)") (class "Default")
      (node (ref "R4") (pin "1") (pinfunction "1_1") (pintype "passive"))
      (node (ref "U3") (pin "4") (pinfunction "G_4") (pintype "passive"))
    )
    (net (code "35") (name "Net-(U4-BST)") (class "Default")
      (node (ref "C19") (pin "1") (pinfunction "1_1") (pintype "passive"))
      (node (ref "U4") (pin "4") (pinfunction "BST_4") (pintype "passive"))
    )
    (net (code "36") (name "Net-(U4-FB)") (class "Default")
      (node (ref "C27") (pin "2") (pinfunction "2_2") (pintype "passive"))
      (node (ref "R10") (pin "2") (pinfunction "2_2") (pintype "passive"))
      (node (ref "R9") (pin "1") (pinfunction "1_1") (pintype "passive"))
      (node (ref "U4") (pin "7") (pinfunction "FB_7") (pintype "input"))
    )
    (net (code "37") (name "Net-(U4-NC)") (class "Default")
      (node (ref "L2") (pin "1") (pinfunction "1_1") (pintype "passive"))
      (node (ref "U4") (pin "12") (pinfunction "SW_12") (pintype "power_in"))
      (node (ref "U4") (pin "3") (pinfunction "NC_3") (pintype "passive"))
    )
    (net (code "38") (name "Net-(U4-VCC)") (class "Default")
      (node (ref "C28") (pin "2") (pinfunction "2_2") (pintype "passive"))
      (node (ref "U4") (pin "5") (pinfunction "VCC_5") (pintype "power_in"))
    )
    (net (code "39") (name "Net-(U5-CBOOT)") (class "Default")
      (node (ref "C25") (pin "1") (pinfunction "1_1") (pintype "passive"))
      (node (ref "U5") (pin "5") (pinfunction "CBOOT_5") (pintype "passive"))
    )
    (net (code "40") (name "Net-(U5-GATE)") (class "Default")
      (node (ref "R4") (pin "2") (pinfunction "2_2") (pintype "passive"))
      (node (ref "U5") (pin "7") (pinfunction "GATE_7") (pintype "passive"))
    )
    (net (code "41") (name "Net-(U5-PTC)") (class "Default")
      (node (ref "RT1") (pin "2") (pinfunction "2_2") (pintype "passive"))
      (node (ref "U5") (pin "2") (pinfunction "PTC_2") (pintype "passive"))
    )
    (net (code "42") (name "Net-(U5-VDS)") (class "Default")
      (node (ref "R5") (pin "1") (pinfunction "1_1") (pintype "passive"))
      (node (ref "U5") (pin "1") (pinfunction "VDS_1") (pintype "passive"))
    )
    (net (code "43") (name "Net-(U6-ADDR)") (class "Default")
      (node (ref "R17") (pin "2") (pinfunction "2_2") (pintype "passive"))
      (node (ref "R20") (pin "2") (pinfunction "2_2") (pintype "passive"))
      (node (ref "U6") (pin "5") (pinfunction "ADDR_5") (pintype "input"))
    )
    (net (code "44") (name "Net-(U6-EN_N)") (class "Default")
      (node (ref "R22") (pin "1") (pinfunction "1_1") (pintype "passive"))
      (node (ref "U6") (pin "11") (pinfunction "EN_N_11") (pintype "input"))
    )
    (net (code "45") (name "Net-(U6-PORT)") (class "Default")
      (node (ref "R21") (pin "2") (pinfunction "2_2") (pintype "passive"))
      (node (ref "U6") (pin "3") (pinfunction "PORT_3") (pintype "input"))
    )
    (net (code "46") (name "Net-(U6-VBUS_DET)") (class "Default")
      (node (ref "R14") (pin "1") (pinfunction "1_1") (pintype "passive"))
      (node (ref "U6") (pin "4") (pinfunction "VBUS_DET_4") (pintype "input"))
    )
    (net (code "47") (name "Net-(U6-VDD)") (class "Default")
      (node (ref "C35") (pin "1") (pinfunction "1_1") (pintype "passive"))
      (node (ref "R11") (pin "1") (pinfunction "1_1") (pintype "passive"))
      (node (ref "R12") (pin "1") (pinfunction "1_1") (pintype "passive"))
      (node (ref "R17") (pin "1") (pinfunction "1_1") (pintype "passive"))
      (node (ref "U6") (pin "12") (pinfunction "VDD_12") (pintype "power_in"))
    )
    (net (code "48") (name "Net-(U7-SW)") (class "Default")
      (node (ref "L3") (pin "1") (pinfunction "1_1") (pintype "passive"))
      (node (ref "U7") (pin "9") (pinfunction "SW_9") (pintype "output"))
    )
    (net (code "49") (name "Net-(U7-VIN)") (class "Default")
      (node (ref "C29") (pin "1") (pinfunction "1_1") (pintype "passive"))
      (node (ref "R15") (pin "1") (pinfunction "1_1") (pintype "passive"))
      (node (ref "R16") (pin "1") (pinfunction "1_1") (pintype "passive"))
      (node (ref "U7") (pin "2") (pinfunction "VIN_2") (pintype "power_in"))
    )
    (net (code "50") (name "Net-(U8-CD)") (class "Default")
      (node (ref "C33") (pin "1") (pinfunction "1_1") (pintype "passive"))
      (node (ref "U8") (pin "4") (pinfunction "CD_4") (pintype "passive"))
    )
    (net (code "51") (name "Net-(U8-VC1)") (class "Default")
      (node (ref "C30") (pin "2") (pinfunction "2_2") (pintype "passive"))
      (node (ref "C32") (pin "1") (pinfunction "1_1") (pintype "passive"))
      (node (ref "R19") (pin "2") (pinfunction "2_2") (pintype "passive"))
      (node (ref "U8") (pin "2") (pinfunction "VC1_2") (pintype "input"))
    )
    (net (code "52") (name "Net-(U8-VC1_CB)") (class "Default")
      (node (ref "R23") (pin "2") (pinfunction "2_2") (pintype "passive"))
      (node (ref "U8") (pin "3") (pinfunction "VC1_CB_3") (pintype "input"))
    )
    (net (code "53") (name "Net-(U8-VC2)") (class "Default")
      (node (ref "C30") (pin "1") (pinfunction "1_1") (pintype "passive"))
      (node (ref "R18") (pin "2") (pinfunction "2_2") (pintype "passive"))
      (node (ref "U8") (pin "1") (pinfunction "VC2_1") (pintype "input"))
    )
    (net (code "54") (name "Net-(U8-VDD)") (class "Default")
      (node (ref "C34") (pin "1") (pinfunction "1_1") (pintype "passive"))
      (node (ref "R13") (pin "2") (pinfunction "2_2") (pintype "passive"))
      (node (ref "U8") (pin "7") (pinfunction "VDD_7") (pintype "power_in"))
    )
    (net (code "55") (name "Regn") (class "Default")
      (node (ref "C16") (pin "2") (pinfunction "2_2") (pintype "passive"))
      (node (ref "R11") (pin "2") (pinfunction "2_2") (pintype "passive"))
      (node (ref "R2") (pin "2") (pinfunction "2_2") (pintype "passive"))
      (node (ref "R8") (pin "2") (pinfunction "2_2") (pintype "passive"))
      (node (ref "U1") (pin "5") (pinfunction "REGN_5") (pintype "passive"))
    )
    (net (code "56") (name "Sys") (class "Default")
      (node (ref "C10") (pin "1") (pinfunction "1_1") (pintype "passive"))
      (node (ref "C11") (pin "1") (pinfunction "1_1") (pintype "passive"))
      (node (ref "C12") (pin "1") (pinfunction "1_1") (pintype "passive"))
      (node (ref "C13") (pin "1") (pinfunction "1_1") (pintype "passive"))
      (node (ref "C14") (pin "1") (pinfunction "1_1") (pintype "passive"))
      (node (ref "C15") (pin "1") (pinfunction "1_1") (pintype "passive"))
      (node (ref "C20") (pin "1") (pinfunction "1_1") (pintype "passive"))
      (node (ref "C21") (pin "1") (pinfunction "1_1") (pintype "passive"))
      (node (ref "C22") (pin "1") (pinfunction "1_1") (pintype "passive"))
      (node (ref "R15") (pin "2") (pinfunction "2_2") (pintype "passive"))
      (node (ref "U1") (pin "25") (pinfunction "SYS_25") (pintype "passive"))
      (node (ref "U4") (pin "10") (pinfunction "VIN_10") (pintype "power_in"))
      (node (ref "U4") (pin "2") (pinfunction "VIN_2") (pintype "power_in"))
    )
    (net (code "57") (name "VbatIn") (class "Default")
      (node (ref "C17") (pin "1") (pinfunction "1_1") (pintype "passive"))
      (node (ref "C18") (pin "1") (pinfunction "1_1") (pintype "passive"))
      (node (ref "C26") (pin "1") (pinfunction "1_1") (pintype "passive"))
      (node (ref "R13") (pin "1") (pinfunction "1_1") (pintype "passive"))
      (node (ref "R16") (pin "2") (pinfunction "2_2") (pintype "passive"))
      (node (ref "R18") (pin "1") (pinfunction "1_1") (pintype "passive"))
      (node (ref "R3") (pin "2") (pinfunction "2_2") (pintype "passive"))
      (node (ref "R5") (pin "2") (pinfunction "2_2") (pintype "passive"))
      (node (ref "RT1") (pin "1") (pinfunction "1_1") (pintype "passive"))
      (node (ref "U2") (pin "5") (pinfunction "D_5") (pintype "passive"))
      (node (ref "U2") (pin "6") (pinfunction "D_6") (pintype "passive"))
      (node (ref "U2") (pin "7") (pinfunction "D_7") (pintype "passive"))
      (node (ref "U2") (pin "8") (pinfunction "D_8") (pintype "passive"))
      (node (ref "U3") (pin "5") (pinfunction "D_5") (pintype "passive"))
      (node (ref "U3") (pin "6") (pinfunction "D_6") (pintype "passive"))
      (node (ref "U3") (pin "7") (pinfunction "D_7") (pintype "passive"))
      (node (ref "U3") (pin "8") (pinfunction "D_8") (pintype "passive"))
      (node (ref "U5") (pin "8") (pinfunction "VCC_8") (pintype "passive"))
      (node (ref "X1") (pin "1") (pinfunction "POS_1") (pintype "passive"))
      (node (ref "X5") (pin "1") (pinfunction "1_1") (pintype "passive"))
    )
    (net (code "58") (name "VbatOut") (class "Default")
      (node (ref "C25") (pin "2") (pinfunction "2_2") (pintype "passive"))
      (node (ref "U3") (pin "1") (pinfunction "S_1") (pintype "passive"))
      (node (ref "U3") (pin "2") (pinfunction "S_2") (pintype "passive"))
      (node (ref "U3") (pin "3") (pinfunction "S_3") (pintype "passive"))
      (node (ref "U5") (pin "6") (pinfunction "SOURCE_6") (pintype "passive"))
      (node (ref "X2") (pin "2") (pinfunction "POS_2") (pintype "passive"))
    )
    (net (code "59") (name "Vbus") (class "Default")
      (node (ref "C2") (pin "1") (pinfunction "1_1") (pintype "passive"))
      (node (ref "C3") (pin "1") (pinfunction "1_1") (pintype "passive"))
      (node (ref "C4") (pin "1") (pinfunction "1_1") (pintype "passive"))
      (node (ref "R14") (pin "2") (pinfunction "2_2") (pintype "passive"))
      (node (ref "U1") (pin "2") (pinfunction "VBUS_2") (pintype "power_in"))
      (node (ref "U1") (pin "3") (pinfunction "VBUS_3") (pintype "power_in"))
      (node (ref "U1") (pin "8") (pinfunction "VAC2_8") (pintype "power_in"))
      (node (ref "U1") (pin "9") (pinfunction "VAC1_9") (pintype "power_in"))
      (node (ref "X4") (pin "A4_B9") (pinfunction "VBUS_A4_B9") (pintype "power_in"))
      (node (ref "X4") (pin "B4_A9") (pinfunction "VBUS_B4_A9") (pintype "power_in"))
    )
    (net (code "60") (name "unconnected-(U1-STAT-Pad1)") (class "Default")
      (node (ref "U1") (pin "1") (pinfunction "STAT_1") (pintype "passive+no_connect"))
    )
    (net (code "61") (name "unconnected-(U6-ID-Pad9)") (class "Default")
      (node (ref "U6") (pin "9") (pinfunction "ID_9") (pintype "open_collector+no_connect"))
    )
    (net (code "62") (name "unconnected-(U10-NRST-Pad4)") (class "Default")
      (node (ref "U10") (pin "4") (pinfunction "NRST_4") (pintype "bidirectional"))
    )
    (net (code "63") (name "unconnected-(U10-PA0-Pad6)") (class "Default")
      (node (ref "U10") (pin "6") (pinfunction "PA0_6") (pintype "bidirectional"))
    )
    (net (code "64") (name "unconnected-(U10-PA1-Pad7)") (class "Default")
      (node (ref "U10") (pin "7") (pinfunction "PA1_7") (pintype "bidirectional"))
    )
    (net (code "65") (name "unconnected-(U10-PA2-Pad8)") (class "Default")
      (node (ref "U10") (pin "8") (pinfunction "PA2_8") (pintype "bidirectional"))
    )
    (net (code "66") (name "unconnected-(U10-PA3-Pad9)") (class "Default")
      (node (ref "U10") (pin "9") (pinfunction "PA3_9") (pintype "bidirectional"))
    )
    (net (code "67") (name "unconnected-(U10-PA4-Pad10)") (class "Default")
      (node (ref "U10") (pin "10") (pinfunction "PA4_10") (pintype "bidirectional"))
    )
    (net (code "68") (name "unconnected-(U10-PA5-Pad11)") (class "Default")
      (node (ref "U10") (pin "11") (pinfunction "PA5_11") (pintype "bidirectional"))
    )
    (net (code "69") (name "unconnected-(U10-PA6-Pad12)") (class "Default")
      (node (ref "U10") (pin "12") (pinfunction "PA6_12") (pintype "bidirectional"))
    )
    (net (code "70") (name "unconnected-(U10-PA7-Pad13)") (class "Default")
      (node (ref "U10") (pin "13") (pinfunction "PA7_13") (pintype "bidirectional"))
    )
    (net (code "71") (name "unconnected-(U10-PA9[PA11]-Pad19)") (class "Default")
      (node (ref "U10") (pin "19") (pinfunction "PA9[PA11]_19") (pintype "bidirectional"))
    )
    (net (code "72") (name "unconnected-(U10-PA10[PA12]-Pad20)") (class "Default")
      (node (ref "U10") (pin "20") (pinfunction "PA10[PA12]_20") (pintype "bidirectional"))
    )
    (net (code "73") (name "unconnected-(U10-PA13-Pad21)") (class "Default")
      (node (ref "U10") (pin "21") (pinfunction "PA13_21") (pintype "bidirectional"))
    )
    (net (code "74") (name "unconnected-(U10-PA14-Pad22)") (class "Default")
      (node (ref "U10") (pin "22") (pinfunction "PA14_22") (pintype "bidirectional"))
    )
    (net (code "75") (name "unconnected-(U10-PA15-Pad23)") (class "Default")
      (node (ref "U10") (pin "23") (pinfunction "PA15_23") (pintype "bidirectional"))
    )
    (net (code "76") (name "unconnected-(U10-PB0-Pad14)") (class "Default")
      (node (ref "U10") (pin "14") (pinfunction "PB0_14") (pintype "bidirectional"))
    )
    (net (code "77") (name "unconnected-(U10-PB1-Pad15)") (class "Default")
      (node (ref "U10") (pin "15") (pinfunction "PB1_15") (pintype "bidirectional"))
    )
    (net (code "78") (name "unconnected-(U10-PB3-Pad24)") (class "Default")
      (node (ref "U10") (pin "24") (pinfunction "PB3_24") (pintype "bidirectional"))
    )
    (net (code "79") (name "unconnected-(U10-PB4-Pad25)") (class "Default")
      (node (ref "U10") (pin "25") (pinfunction "PB4_25") (pintype "bidirectional"))
    )
    (net (code "80") (name "unconnected-(U10-PB5-Pad26)") (class "Default")
      (node (ref "U10") (pin "26") (pinfunction "PB5_26") (pintype "bidirectional"))
    )
    (net (code "81") (name "unconnected-(U10-PB6-Pad27)") (class "Default")
      (node (ref "U10") (pin "27") (pinfunction "PB6_27") (pintype "bidirectional"))
    )
    (net (code "82") (name "unconnected-(U10-PB7-Pad28)") (class "Default")
      (node (ref "U10") (pin "28") (pinfunction "PB7_28") (pintype "bidirectional"))
    )
    (net (code "83") (name "unconnected-(U10-PB8-BOOT0-Pad1)") (class "Default")
      (node (ref "U10") (pin "1") (pinfunction "PB8-BOOT0_1") (pintype "bidirectional"))
    )
    (net (code "84") (name "unconnected-(U10-PF0-OSC_IN-Pad2)") (class "Default")
      (node (ref "U10") (pin "2") (pinfunction "PF0-OSC_IN_2") (pintype "bidirectional"))
    )
    (net (code "85") (name "unconnected-(U10-PF1-OSC_OUT-Pad3)") (class "Default")
      (node (ref "U10") (pin "3") (pinfunction "PF1-OSC_OUT_3") (pintype "bidirectional"))
    )
    (net (code "86") (name "unconnected-(U10-VDD-Pad17)") (class "Default")
      (node (ref "U10") (pin "17") (pinfunction "VDD_17") (pintype "power_in"))
    )
    (net (code "87") (name "unconnected-(U10-VDDA-Pad5)") (class "Default")
      (node (ref "U10") (pin "5") (pinfunction "VDDA_5") (pintype "power_in"))
    )
    (net (code "88") (name "unconnected-(U10-VDDIO2-Pad18)") (class "Default")
      (node (ref "U10") (pin "18") (pinfunction "VDDIO2_18") (pintype "power_in"))
    )
    (net (code "89") (name "unconnected-(U10-VSS-Pad16)") (class "Default")
      (node (ref "U10") (pin "16") (pinfunction "VSS_16") (pintype "power_in"))
    )
    (net (code "90") (name "unconnected-(X1-NC-PadS1)") (class "Default")
      (node (ref "X1") (pin "S1") (pinfunction "NC_S1") (pintype "passive+no_connect"))
    )
    (net (code "91") (name "unconnected-(X1-NC-PadS2)") (class "Default")
      (node (ref "X1") (pin "S2") (pinfunction "NC_S2") (pintype "passive+no_connect"))
    )
    (net (code "92") (name "unconnected-(X2-NC-PadS1)") (class "Default")
      (node (ref "X2") (pin "S1") (pinfunction "NC_S1") (pintype "passive+no_connect"))
    )
    (net (code "93") (name "unconnected-(X2-NC-PadS2)") (class "Default")
      (node (ref "X2") (pin "S2") (pinfunction "NC_S2") (pintype "passive+no_connect"))
    )
    (net (code "94") (name "unconnected-(X4-SBU1-PadA8)") (class "Default")
      (node (ref "X4") (pin "A8") (pinfunction "SBU1_A8") (pintype "bidirectional+no_connect"))
    )
    (net (code "95") (name "unconnected-(X4-SBU2-PadB8)") (class "Default")
      (node (ref "X4") (pin "B8") (pinfunction "SBU2_B8") (pintype "bidirectional+no_connect"))
    )
    (net (code "96") (name "unconnected-(Z1-Pad1)") (class "Default")
      (node (ref "Z1") (pin "1") (pinfunction "1_1") (pintype "passive"))
    )
    (net (code "97") (name "unconnected-(Z1-Pad2)") (class "Default")
      (node (ref "Z1") (pin "2") (pinfunction "2_2") (pintype "passive"))
    )
  )
)
